# Thermo.net
KiCad netlist of a schematic drawn in Altium Designer
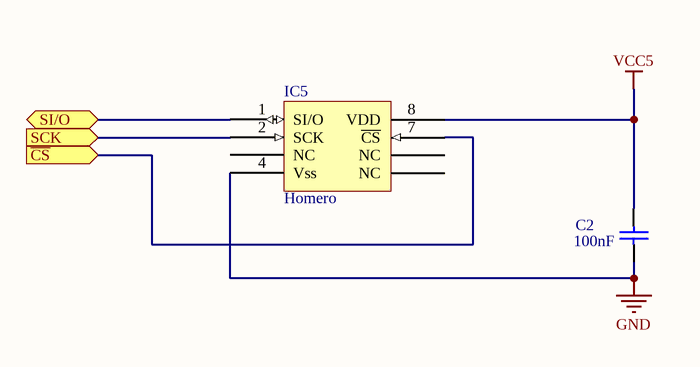
[diagram p0: Thermo.SchDoc]

(export (version "E")
  (design (tool "Eeschema 10.0.6"))
  (components
    (comp (ref "C2")
      (value "100nF")
      (footprint "FP_0805_CAP_085")
      (description "Capacitor")
      (fields (field (name "TOLERANCE") "+80%/-20%") (field (name "VOLTAGE") "25V"))
      (libsource (lib "hallglib") (part "CAP 100nF"))
    )
    (comp (ref "IC5")
      (value "Homero")
      (footprint "FP_SO8_MS012AA")
      (libsource (lib "iao0w2") (part "Homero"))
    )
  )
  (nets
    (net (code "1") (name "/SCK") (class "Default")
      (node (ref "IC5") (pin "2") (pinfunction "SCK_2") (pintype "input"))
    )
    (net (code "2") (name "/SI{slash}O") (class "Default")
      (node (ref "IC5") (pin "1") (pinfunction "SI/O_1") (pintype "bidirectional"))
    )
    (net (code "3") (name "/~{CS}") (class "Default")
      (node (ref "IC5") (pin "7") (pinfunction "~{CS}_7") (pintype "input"))
    )
    (net (code "4") (name "GND") (class "Default")
      (node (ref "C2") (pin "1") (pinfunction "1_1") (pintype "passive"))
      (node (ref "IC5") (pin "4") (pinfunction "Vss_4") (pintype "passive"))
    )
    (net (code "5") (name "VCC5") (class "Default")
      (node (ref "C2") (pin "2") (pinfunction "2_2") (pintype "passive"))
      (node (ref "IC5") (pin "8") (pinfunction "VDD_8") (pintype "passive"))
    )
    (net (code "6") (name "unconnected-(IC5-NC-Pad3)") (class "Default")
      (node (ref "IC5") (pin "3") (pinfunction "NC_3") (pintype "passive"))
    )
    (net (code "7") (name "unconnected-(IC5-NC-Pad5)") (class "Default")
      (node (ref "IC5") (pin "5") (pinfunction "NC_5") (pintype "passive"))
    )
    (net (code "8") (name "unconnected-(IC5-NC-Pad6)") (class "Default")
      (node (ref "IC5") (pin "6") (pinfunction "NC_6") (pintype "passive"))
    )
  )
)
